# Capstone_V4.net
KiCad netlist of a schematic drawn in EAGLE
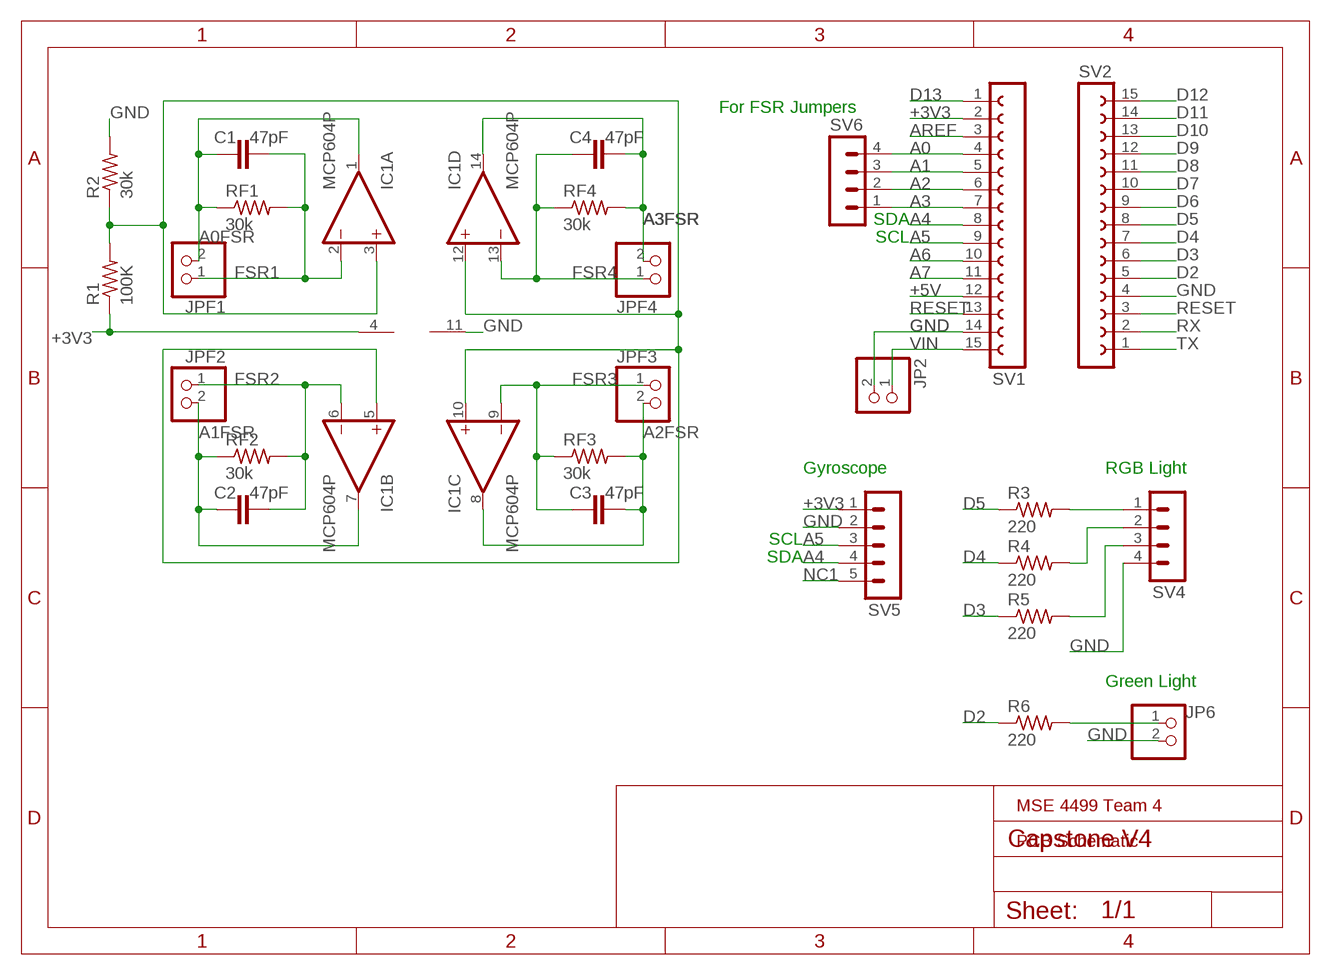
[diagram p0: schematic, sheet 1]

(export (version "E")
  (design (tool "Eeschema 10.0.6"))
  (components
    (comp (ref "C1")
      (value "47pF")
      (footprint "eagle-import:C2.5-3")
      (libsource (lib "eagle-import") (part "C2,5-3"))
    )
    (comp (ref "C2")
      (value "47pF")
      (footprint "eagle-import:C2.5-3")
      (libsource (lib "eagle-import") (part "C2,5-3"))
    )
    (comp (ref "C3")
      (value "47pF")
      (footprint "eagle-import:C2.5-3")
      (libsource (lib "eagle-import") (part "C2,5-3"))
    )
    (comp (ref "C4")
      (value "47pF")
      (footprint "eagle-import:C2.5-3")
      (libsource (lib "eagle-import") (part "C2,5-3"))
    )
    (comp (ref "IC1")
      (value "MCP604P")
      (footprint "eagle-import:DIL14")
      (libsource (lib "eagle-import") (part "MCP604P"))
    )
    (comp (ref "JP2")
      (value "PINHD-1X2")
      (footprint "eagle-import:1X02")
      (libsource (lib "eagle-import") (part "PINHD-1X2"))
    )
    (comp (ref "JP6")
      (value "PINHD-1X2")
      (footprint "eagle-import:1X02")
      (libsource (lib "eagle-import") (part "PINHD-1X2"))
    )
    (comp (ref "JPF1")
      (value "PINHD-1X2")
      (footprint "eagle-import:1X02")
      (libsource (lib "eagle-import") (part "PINHD-1X2"))
    )
    (comp (ref "JPF2")
      (value "PINHD-1X2")
      (footprint "eagle-import:1X02")
      (libsource (lib "eagle-import") (part "PINHD-1X2"))
    )
    (comp (ref "JPF3")
      (value "PINHD-1X2")
      (footprint "eagle-import:1X02")
      (libsource (lib "eagle-import") (part "PINHD-1X2"))
    )
    (comp (ref "JPF4")
      (value "PINHD-1X2")
      (footprint "eagle-import:1X02")
      (libsource (lib "eagle-import") (part "PINHD-1X2"))
    )
    (comp (ref "R1")
      (value "100K")
      (footprint "eagle-import:0204_7")
      (libsource (lib "eagle-import") (part "R-US_0204/7"))
    )
    (comp (ref "R2")
      (value "30k")
      (footprint "eagle-import:0204_7")
      (libsource (lib "eagle-import") (part "R-US_0204/7"))
    )
    (comp (ref "R3")
      (value "220")
      (footprint "eagle-import:0204_7")
      (libsource (lib "eagle-import") (part "R-US_0204/7"))
    )
    (comp (ref "R4")
      (value "220")
      (footprint "eagle-import:0204_7")
      (libsource (lib "eagle-import") (part "R-US_0204/7"))
    )
    (comp (ref "R5")
      (value "220")
      (footprint "eagle-import:0204_7")
      (libsource (lib "eagle-import") (part "R-US_0204/7"))
    )
    (comp (ref "R6")
      (value "220")
      (footprint "eagle-import:0204_7")
      (libsource (lib "eagle-import") (part "R-US_0204/7"))
    )
    (comp (ref "RF1")
      (value "30k")
      (footprint "eagle-import:0204_7")
      (libsource (lib "eagle-import") (part "R-US_0204/7"))
    )
    (comp (ref "RF2")
      (value "30k")
      (footprint "eagle-import:0204_7")
      (libsource (lib "eagle-import") (part "R-US_0204/7"))
    )
    (comp (ref "RF3")
      (value "30k")
      (footprint "eagle-import:0204_7")
      (libsource (lib "eagle-import") (part "R-US_0204/7"))
    )
    (comp (ref "RF4")
      (value "30k")
      (footprint "eagle-import:0204_7")
      (libsource (lib "eagle-import") (part "R-US_0204/7"))
    )
    (comp (ref "SV1")
      (value "FE15-1")
      (footprint "eagle-import:FE15")
      (libsource (lib "eagle-import") (part "FE15-1"))
    )
    (comp (ref "SV2")
      (value "FE15-1")
      (footprint "eagle-import:FE15")
      (libsource (lib "eagle-import") (part "FE15-1"))
    )
    (comp (ref "SV4")
      (value "MA04-1")
      (footprint "eagle-import:MA04-1")
      (libsource (lib "eagle-import") (part "MA04-1"))
    )
    (comp (ref "SV5")
      (value "MA05-1")
      (footprint "eagle-import:MA05-1")
      (libsource (lib "eagle-import") (part "MA05-1"))
    )
    (comp (ref "SV6")
      (value "MA04-1")
      (footprint "eagle-import:MA04-1")
      (libsource (lib "eagle-import") (part "MA04-1"))
    )
  )
  (nets
    (net (code "1") (name "/+3V3") (class "Default")
      (node (ref "IC1") (pin "4") (pinfunction "V+_4") (pintype "power_in"))
      (node (ref "R1") (pin "1") (pinfunction "1_1") (pintype "passive"))
      (node (ref "SV1") (pin "2") (pinfunction "2_2") (pintype "passive"))
      (node (ref "SV5") (pin "1") (pinfunction "1_1") (pintype "passive"))
    )
    (net (code "2") (name "/+5V") (class "Default")
      (node (ref "SV1") (pin "12") (pinfunction "12_12") (pintype "passive"))
    )
    (net (code "3") (name "/A0") (class "Default")
      (node (ref "SV1") (pin "4") (pinfunction "4_4") (pintype "passive"))
      (node (ref "SV6") (pin "4") (pinfunction "4_4") (pintype "passive"))
    )
    (net (code "4") (name "/A0FSR") (class "Default")
      (node (ref "C1") (pin "1") (pinfunction "1_1") (pintype "passive"))
      (node (ref "IC1") (pin "1") (pinfunction "OUT_1") (pintype "output"))
      (node (ref "JPF1") (pin "2") (pinfunction "2_2") (pintype "passive"))
      (node (ref "RF1") (pin "1") (pinfunction "1_1") (pintype "passive"))
    )
    (net (code "5") (name "/A1") (class "Default")
      (node (ref "SV1") (pin "5") (pinfunction "5_5") (pintype "passive"))
      (node (ref "SV6") (pin "3") (pinfunction "3_3") (pintype "passive"))
    )
    (net (code "6") (name "/A1FSR") (class "Default")
      (node (ref "C2") (pin "1") (pinfunction "1_1") (pintype "passive"))
      (node (ref "IC1") (pin "7") (pinfunction "OUT_7") (pintype "output"))
      (node (ref "JPF2") (pin "2") (pinfunction "2_2") (pintype "passive"))
      (node (ref "RF2") (pin "1") (pinfunction "1_1") (pintype "passive"))
    )
    (net (code "7") (name "/A2") (class "Default")
      (node (ref "SV1") (pin "6") (pinfunction "6_6") (pintype "passive"))
      (node (ref "SV6") (pin "2") (pinfunction "2_2") (pintype "passive"))
    )
    (net (code "8") (name "/A2FSR") (class "Default")
      (node (ref "C3") (pin "2") (pinfunction "2_2") (pintype "passive"))
      (node (ref "IC1") (pin "8") (pinfunction "OUT_8") (pintype "output"))
      (node (ref "JPF3") (pin "2") (pinfunction "2_2") (pintype "passive"))
      (node (ref "RF3") (pin "2") (pinfunction "2_2") (pintype "passive"))
    )
    (net (code "9") (name "/A3") (class "Default")
      (node (ref "SV1") (pin "7") (pinfunction "7_7") (pintype "passive"))
      (node (ref "SV6") (pin "1") (pinfunction "1_1") (pintype "passive"))
    )
    (net (code "10") (name "/A3FSR") (class "Default")
      (node (ref "C4") (pin "2") (pinfunction "2_2") (pintype "passive"))
      (node (ref "IC1") (pin "14") (pinfunction "OUT_14") (pintype "output"))
      (node (ref "JPF4") (pin "2") (pinfunction "2_2") (pintype "passive"))
      (node (ref "RF4") (pin "2") (pinfunction "2_2") (pintype "passive"))
    )
    (net (code "11") (name "/A4") (class "Default")
      (node (ref "SV1") (pin "8") (pinfunction "8_8") (pintype "passive"))
      (node (ref "SV5") (pin "4") (pinfunction "4_4") (pintype "passive"))
    )
    (net (code "12") (name "/A5") (class "Default")
      (node (ref "SV1") (pin "9") (pinfunction "9_9") (pintype "passive"))
      (node (ref "SV5") (pin "3") (pinfunction "3_3") (pintype "passive"))
    )
    (net (code "13") (name "/A6") (class "Default")
      (node (ref "SV1") (pin "10") (pinfunction "10_10") (pintype "passive"))
    )
    (net (code "14") (name "/A7") (class "Default")
      (node (ref "SV1") (pin "11") (pinfunction "11_11") (pintype "passive"))
    )
    (net (code "15") (name "/AREF") (class "Default")
      (node (ref "SV1") (pin "3") (pinfunction "3_3") (pintype "passive"))
    )
    (net (code "16") (name "/D2") (class "Default")
      (node (ref "R6") (pin "1") (pinfunction "1_1") (pintype "passive"))
      (node (ref "SV2") (pin "5") (pinfunction "5_5") (pintype "passive"))
    )
    (net (code "17") (name "/D3") (class "Default")
      (node (ref "R5") (pin "1") (pinfunction "1_1") (pintype "passive"))
      (node (ref "SV2") (pin "6") (pinfunction "6_6") (pintype "passive"))
    )
    (net (code "18") (name "/D4") (class "Default")
      (node (ref "R4") (pin "1") (pinfunction "1_1") (pintype "passive"))
      (node (ref "SV2") (pin "7") (pinfunction "7_7") (pintype "passive"))
    )
    (net (code "19") (name "/D5") (class "Default")
      (node (ref "R3") (pin "1") (pinfunction "1_1") (pintype "passive"))
      (node (ref "SV2") (pin "8") (pinfunction "8_8") (pintype "passive"))
    )
    (net (code "20") (name "/D6") (class "Default")
      (node (ref "SV2") (pin "9") (pinfunction "9_9") (pintype "passive"))
    )
    (net (code "21") (name "/D7") (class "Default")
      (node (ref "SV2") (pin "10") (pinfunction "10_10") (pintype "passive"))
    )
    (net (code "22") (name "/D8") (class "Default")
      (node (ref "SV2") (pin "11") (pinfunction "11_11") (pintype "passive"))
    )
    (net (code "23") (name "/D9") (class "Default")
      (node (ref "SV2") (pin "12") (pinfunction "12_12") (pintype "passive"))
    )
    (net (code "24") (name "/D10") (class "Default")
      (node (ref "SV2") (pin "13") (pinfunction "13_13") (pintype "passive"))
    )
    (net (code "25") (name "/D11") (class "Default")
      (node (ref "SV2") (pin "14") (pinfunction "14_14") (pintype "passive"))
    )
    (net (code "26") (name "/D12") (class "Default")
      (node (ref "SV2") (pin "15") (pinfunction "15_15") (pintype "passive"))
    )
    (net (code "27") (name "/D13") (class "Default")
      (node (ref "SV1") (pin "1") (pinfunction "1_1") (pintype "passive"))
    )
    (net (code "28") (name "/FSR1") (class "Default")
      (node (ref "C1") (pin "2") (pinfunction "2_2") (pintype "passive"))
      (node (ref "IC1") (pin "2") (pinfunction "-IN_2") (pintype "input"))
      (node (ref "JPF1") (pin "1") (pinfunction "1_1") (pintype "passive"))
      (node (ref "RF1") (pin "2") (pinfunction "2_2") (pintype "passive"))
    )
    (net (code "29") (name "/FSR2") (class "Default")
      (node (ref "C2") (pin "2") (pinfunction "2_2") (pintype "passive"))
      (node (ref "IC1") (pin "6") (pinfunction "-IN_6") (pintype "input"))
      (node (ref "JPF2") (pin "1") (pinfunction "1_1") (pintype "passive"))
      (node (ref "RF2") (pin "2") (pinfunction "2_2") (pintype "passive"))
    )
    (net (code "30") (name "/FSR3") (class "Default")
      (node (ref "C3") (pin "1") (pinfunction "1_1") (pintype "passive"))
      (node (ref "IC1") (pin "9") (pinfunction "-IN_9") (pintype "input"))
      (node (ref "JPF3") (pin "1") (pinfunction "1_1") (pintype "passive"))
      (node (ref "RF3") (pin "1") (pinfunction "1_1") (pintype "passive"))
    )
    (net (code "31") (name "/FSR4") (class "Default")
      (node (ref "C4") (pin "1") (pinfunction "1_1") (pintype "passive"))
      (node (ref "IC1") (pin "13") (pinfunction "-IN_13") (pintype "input"))
      (node (ref "JPF4") (pin "1") (pinfunction "1_1") (pintype "passive"))
      (node (ref "RF4") (pin "1") (pinfunction "1_1") (pintype "passive"))
    )
    (net (code "32") (name "/GND") (class "Default")
      (node (ref "IC1") (pin "11") (pinfunction "V-_11") (pintype "power_in"))
      (node (ref "JP2") (pin "2") (pinfunction "2_2") (pintype "passive"))
      (node (ref "JP6") (pin "2") (pinfunction "2_2") (pintype "passive"))
      (node (ref "R2") (pin "2") (pinfunction "2_2") (pintype "passive"))
      (node (ref "SV1") (pin "14") (pinfunction "14_14") (pintype "passive"))
      (node (ref "SV2") (pin "4") (pinfunction "4_4") (pintype "passive"))
      (node (ref "SV4") (pin "4") (pinfunction "4_4") (pintype "passive"))
      (node (ref "SV5") (pin "2") (pinfunction "2_2") (pintype "passive"))
    )
    (net (code "33") (name "/NC1") (class "Default")
      (node (ref "SV5") (pin "5") (pinfunction "5_5") (pintype "passive"))
    )
    (net (code "34") (name "/RESET") (class "Default")
      (node (ref "SV1") (pin "13") (pinfunction "13_13") (pintype "passive"))
      (node (ref "SV2") (pin "3") (pinfunction "3_3") (pintype "passive"))
    )
    (net (code "35") (name "/RX") (class "Default")
      (node (ref "SV2") (pin "2") (pinfunction "2_2") (pintype "passive"))
    )
    (net (code "36") (name "/TX") (class "Default")
      (node (ref "SV2") (pin "1") (pinfunction "1_1") (pintype "passive"))
    )
    (net (code "37") (name "/VIN") (class "Default")
      (node (ref "JP2") (pin "1") (pinfunction "1_1") (pintype "passive"))
      (node (ref "SV1") (pin "15") (pinfunction "15_15") (pintype "passive"))
    )
    (net (code "38") (name "Net-(IC1A-+IN)") (class "Default")
      (node (ref "IC1") (pin "10") (pinfunction "+IN_10") (pintype "input"))
      (node (ref "IC1") (pin "12") (pinfunction "+IN_12") (pintype "input"))
      (node (ref "IC1") (pin "3") (pinfunction "+IN_3") (pintype "input"))
      (node (ref "IC1") (pin "5") (pinfunction "+IN_5") (pintype "input"))
      (node (ref "R1") (pin "2") (pinfunction "2_2") (pintype "passive"))
      (node (ref "R2") (pin "1") (pinfunction "1_1") (pintype "passive"))
    )
    (net (code "39") (name "Net-(JP6-Pad1)") (class "Default")
      (node (ref "JP6") (pin "1") (pinfunction "1_1") (pintype "passive"))
      (node (ref "R6") (pin "2") (pinfunction "2_2") (pintype "passive"))
    )
    (net (code "40") (name "Net-(R3-Pad2)") (class "Default")
      (node (ref "R3") (pin "2") (pinfunction "2_2") (pintype "passive"))
      (node (ref "SV4") (pin "1") (pinfunction "1_1") (pintype "passive"))
    )
    (net (code "41") (name "Net-(R4-Pad2)") (class "Default")
      (node (ref "R4") (pin "2") (pinfunction "2_2") (pintype "passive"))
      (node (ref "SV4") (pin "2") (pinfunction "2_2") (pintype "passive"))
    )
    (net (code "42") (name "Net-(R5-Pad2)") (class "Default")
      (node (ref "R5") (pin "2") (pinfunction "2_2") (pintype "passive"))
      (node (ref "SV4") (pin "3") (pinfunction "3_3") (pintype "passive"))
    )
  )
)
